# Buck_Converter.net
KiCad netlist of a schematic drawn in Altium Designer
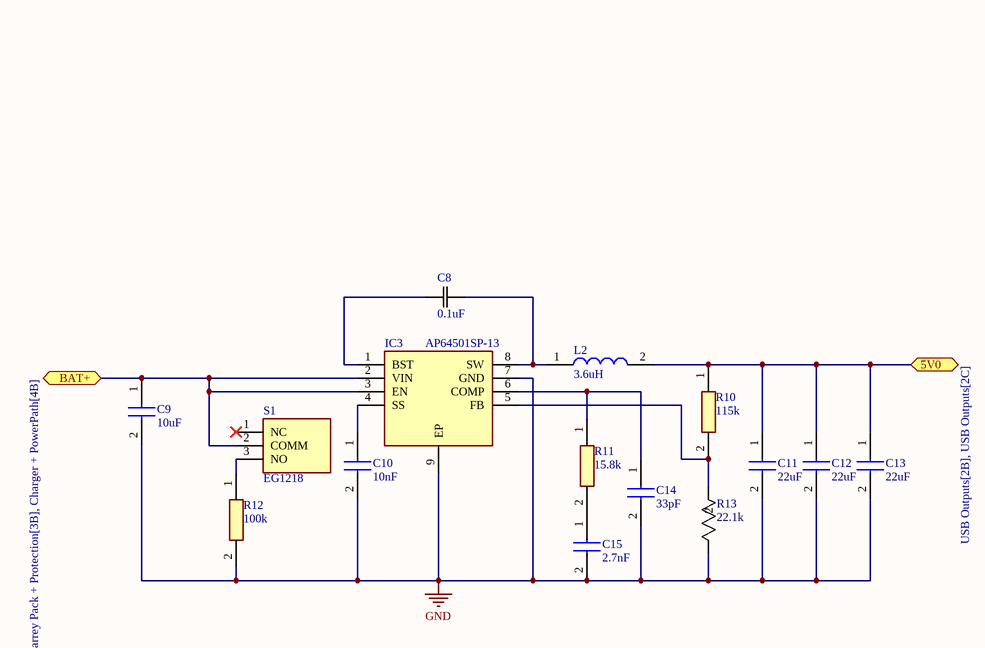
[diagram p0: Buck Converter.SchDoc]

(export (version "E")
  (design (tool "Eeschema 10.0.6"))
  (components
    (comp (ref "C8")
      (value "0.1uF")
      (footprint "CAPC220145_88N_KEM")
      (description "SMD Comm X7R, Ceramic, 0.1 uF, 10%, 50 VDC, X7R, SMD, MLCC, Temperature Stable, Class II, 0805")
      (fields
        (field (name "MANUFACTURER_PART_NUMBER") "C0805C104K5RACTU")
        (field (name "COPYRIGHT") "Copyright (C) 2025 Ultra Librarian. All rights reserved.")
      )
      (libsource (lib "C0805C104K5RACTU") (part "C0805C104K5RACTU"))
    )
    (comp (ref "C9")
      (value "10uF")
      (footprint "SamacSys:CAPC3225X280N")
      (description "Capacitor")
      (fields
        (field (name "MANUFACTURER_PART_NUMBER") "UMJ325KB7106KMHP")
        (field (name "MOUSER PART NUMBER") "963-UMJ325KB7106KMHP")
      )
      (libsource (lib "*") (part "UMJ325KB7106KMHP"))
    )
    (comp (ref "C10")
      (value "10nF")
      (footprint "SamacSys:CAPC2012X88N")
      (description "Capacitor")
      (fields
        (field (name "MANUFACTURER_PART_NUMBER") "C0805C103KAREC7210")
        (field (name "MOUSER PART NUMBER") "80-C0805C103KARECLR")
      )
      (libsource (lib "*") (part "C0805C103KAREC7210"))
    )
    (comp (ref "C11")
      (value "22uF")
      (footprint "SamacSys:C1210")
      (description "Capacitor")
      (fields
        (field (name "MANUFACTURER_PART_NUMBER") "C1210C226K4RACTU")
        (field (name "MOUSER PART NUMBER") "80-C1210C226K4RACTU")
      )
      (libsource (lib "*") (part "C1210C226K4RACTU"))
    )
    (comp (ref "C12")
      (value "22uF")
      (footprint "SamacSys:C1210")
      (description "Capacitor")
      (fields
        (field (name "MANUFACTURER_PART_NUMBER") "C1210C226K4RACTU")
        (field (name "MOUSER PART NUMBER") "80-C1210C226K4RACTU")
      )
      (libsource (lib "*") (part "C1210C226K4RACTU"))
    )
    (comp (ref "C13")
      (value "22uF")
      (footprint "SamacSys:C1210")
      (description "Capacitor")
      (fields
        (field (name "MANUFACTURER_PART_NUMBER") "C1210C226K4RACTU")
        (field (name "MOUSER PART NUMBER") "80-C1210C226K4RACTU")
      )
      (libsource (lib "*") (part "C1210C226K4RACTU"))
    )
    (comp (ref "C14")
      (value "33pF")
      (footprint "SamacSys:CAPC2012X70N")
      (description "Capacitor")
      (fields
        (field (name "MANUFACTURER_PART_NUMBER") "VJ0805A330FXBPW1BC")
        (field (name "MOUSER PART NUMBER") "77-VJ0805A330FXBPBC")
      )
      (libsource (lib "*") (part "VJ0805A330FXBPW1BC"))
    )
    (comp (ref "C15")
      (value "2.7nF")
      (footprint "SamacSys:C0805")
      (description "Capacitor")
      (fields
        (field (name "MANUFACTURER_PART_NUMBER") "C0805C272J5GACTU")
        (field (name "MOUSER PART NUMBER") "80-C0805C272J5GACTU")
      )
      (libsource (lib "*") (part "C0805C272J5GACTU"))
    )
    (comp (ref "IC3")
      (value "AP64501SP-13")
      (footprint "SamacSys:SOIC127P600X163-9N")
      (description "Integrated Circuit")
      (fields (field (name "MOUSER PART NUMBER") "621-AP64501SP-13"))
      (libsource (lib "*") (part "AP64501SP-13"))
    )
    (comp (ref "L2")
      (value "3.6uH")
      (footprint "SamacSys:7447797360")
      (description "Inductor")
      (fields
        (field (name "MANUFACTURER_PART_NUMBER") "7447797360")
        (field (name "MOUSER PART NUMBER") "710-7447797360")
      )
      (libsource (lib "*") (part "7447797360"))
    )
    (comp (ref "R10")
      (value "115k")
      (footprint "SamacSys:RESC2012X60N")
      (description "Resistor")
      (fields
        (field (name "MANUFACTURER_PART_NUMBER") "AC0805FR-07115KL")
        (field (name "MOUSER PART NUMBER") "603-AC0805FR-07115KL")
      )
      (libsource (lib "*") (part "AC0805FR-07115KL"))
    )
    (comp (ref "R11")
      (value "15.8k")
      (footprint "SamacSys:RESC2012X60N")
      (description "Resistor")
      (fields
        (field (name "MANUFACTURER_PART_NUMBER") "RC0805FR-0715K8L")
        (field (name "MOUSER PART NUMBER") "603-RC0805FR-0715K8L")
      )
      (libsource (lib "*") (part "RC0805FR-0715K8L"))
    )
    (comp (ref "R12")
      (value "100k")
      (footprint "SamacSys:RESC2012X60N")
      (description "Resistor")
      (fields (field (name "MANUFACTURER_PART_NUMBER") "CHV0805-FX-1003ELF"))
      (libsource (lib "*") (part "CHV0805-FX-1003ELF"))
    )
    (comp (ref "R13")
      (value "22.1k")
      (footprint "RC0805N_YAG")
      (description "Description")
      (fields
        (field (name "MANUFACTURER_PART_NUMBER") "RC0805FR-0722K1L")
        (field (name "COPYRIGHT") "Copyright (C) 2025 Ultra Librarian. All rights reserved.")
      )
      (libsource (lib "RC0805FR-0722K1L") (part "RC0805FR-0722K1L"))
    )
    (comp (ref "S1")
      (value "EG1218")
      (footprint "SamacSys:EG1218")
      (description "Switch")
      (fields (field (name "MOUSER PART NUMBER") "612-EG1218"))
      (libsource (lib "*") (part "EG1218"))
    )
  )
  (nets
    (net (code "1") (name "/5V0") (class "Default")
      (node (ref "C11") (pin "1") (pinfunction "1_1") (pintype "passive"))
      (node (ref "C12") (pin "1") (pinfunction "1_1") (pintype "passive"))
      (node (ref "C13") (pin "1") (pinfunction "1_1") (pintype "passive"))
      (node (ref "L2") (pin "2") (pinfunction "2_2") (pintype "passive"))
      (node (ref "R10") (pin "1") (pinfunction "1_1") (pintype "passive"))
    )
    (net (code "2") (name "/BAT+") (class "Default")
      (node (ref "C9") (pin "1") (pinfunction "1_1") (pintype "passive"))
      (node (ref "IC3") (pin "2") (pinfunction "VIN_2") (pintype "passive"))
      (node (ref "IC3") (pin "3") (pinfunction "EN_3") (pintype "passive"))
      (node (ref "S1") (pin "2") (pinfunction "COMM_2") (pintype "passive"))
    )
    (net (code "3") (name "GND") (class "Default")
      (node (ref "C10") (pin "2") (pinfunction "2_2") (pintype "passive"))
      (node (ref "C11") (pin "2") (pinfunction "2_2") (pintype "passive"))
      (node (ref "C12") (pin "2") (pinfunction "2_2") (pintype "passive"))
      (node (ref "C13") (pin "2") (pinfunction "2_2") (pintype "passive"))
      (node (ref "C14") (pin "2") (pinfunction "2_2") (pintype "passive"))
      (node (ref "C15") (pin "2") (pinfunction "2_2") (pintype "passive"))
      (node (ref "C9") (pin "2") (pinfunction "2_2") (pintype "passive"))
      (node (ref "IC3") (pin "7") (pinfunction "GND_7") (pintype "passive"))
      (node (ref "IC3") (pin "9") (pinfunction "EP_9") (pintype "passive"))
      (node (ref "R12") (pin "2") (pinfunction "2_2") (pintype "passive"))
      (node (ref "R13") (pin "1") (pinfunction "1_1") (pintype "passive"))
    )
    (net (code "4") (name "Net-(C15-Pad1)") (class "Default")
      (node (ref "C15") (pin "1") (pinfunction "1_1") (pintype "passive"))
      (node (ref "R11") (pin "2") (pinfunction "2_2") (pintype "passive"))
    )
    (net (code "5") (name "Net-(IC3-BST)") (class "Default")
      (node (ref "C8") (pin "2") (pinfunction "2_2") (pintype "passive"))
      (node (ref "IC3") (pin "1") (pinfunction "BST_1") (pintype "passive"))
    )
    (net (code "6") (name "Net-(IC3-COMP)") (class "Default")
      (node (ref "C14") (pin "1") (pinfunction "1_1") (pintype "passive"))
      (node (ref "IC3") (pin "6") (pinfunction "COMP_6") (pintype "passive"))
      (node (ref "R11") (pin "1") (pinfunction "1_1") (pintype "passive"))
    )
    (net (code "7") (name "Net-(IC3-FB)") (class "Default")
      (node (ref "IC3") (pin "5") (pinfunction "FB_5") (pintype "passive"))
      (node (ref "R10") (pin "2") (pinfunction "2_2") (pintype "passive"))
      (node (ref "R13") (pin "2") (pinfunction "2_2") (pintype "passive"))
    )
    (net (code "8") (name "Net-(IC3-SS)") (class "Default")
      (node (ref "C10") (pin "1") (pinfunction "1_1") (pintype "passive"))
      (node (ref "IC3") (pin "4") (pinfunction "SS_4") (pintype "passive"))
    )
    (net (code "9") (name "Net-(IC3-SW)") (class "Default")
      (node (ref "C8") (pin "1") (pinfunction "1_1") (pintype "passive"))
      (node (ref "IC3") (pin "8") (pinfunction "SW_8") (pintype "passive"))
      (node (ref "L2") (pin "1") (pinfunction "1_1") (pintype "passive"))
    )
    (net (code "10") (name "Net-(S1-NO)") (class "Default")
      (node (ref "R12") (pin "1") (pinfunction "1_1") (pintype "passive"))
      (node (ref "S1") (pin "3") (pinfunction "NO_3") (pintype "passive"))
    )
    (net (code "11") (name "unconnected-(S1-NC-Pad1)") (class "Default")
      (node (ref "S1") (pin "1") (pinfunction "NC_1") (pintype "passive+no_connect"))
    )
  )
)
